# BodyTempUnit.net
KiCad netlist of a schematic drawn in EAGLE
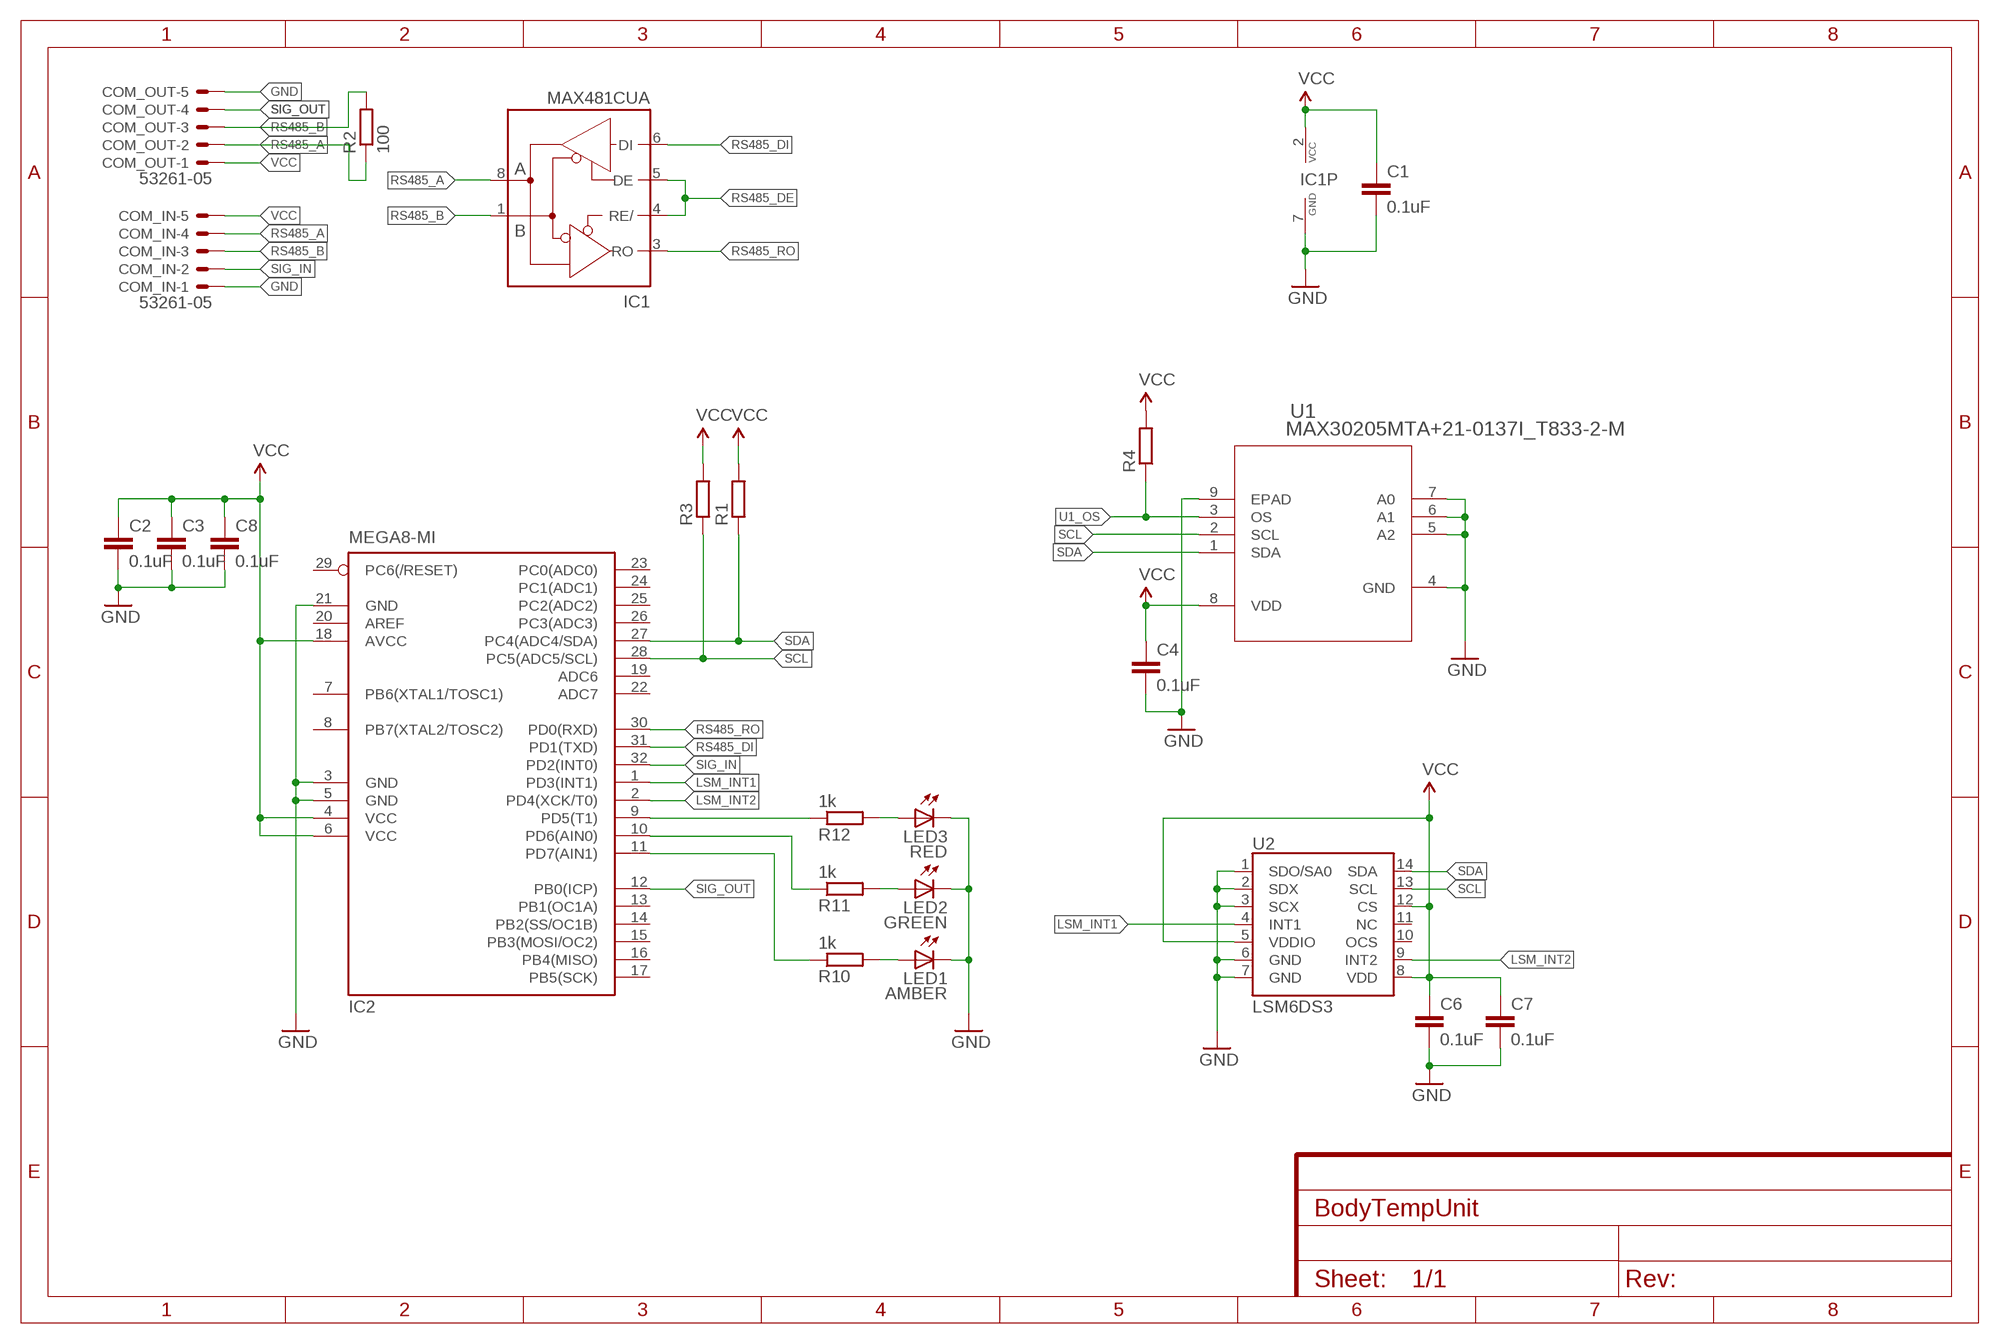
[diagram p0: schematic, sheet 1]

(export (version "E")
  (design (tool "Eeschema 10.0.6"))
  (components
    (comp (ref "C1")
      (value "0.1uF")
      (footprint "eagle-import:C0603K")
      (libsource (lib "eagle-import") (part "C-EUC0603K"))
    )
    (comp (ref "C2")
      (value "0.1uF")
      (footprint "eagle-import:C0603K")
      (libsource (lib "eagle-import") (part "C-EUC0603K"))
    )
    (comp (ref "C3")
      (value "0.1uF")
      (footprint "eagle-import:C0603K")
      (libsource (lib "eagle-import") (part "C-EUC0603K"))
    )
    (comp (ref "C4")
      (value "0.1uF")
      (footprint "eagle-import:C0603K")
      (libsource (lib "eagle-import") (part "C-EUC0603K"))
    )
    (comp (ref "C6")
      (value "0.1uF")
      (footprint "eagle-import:C0603K")
      (libsource (lib "eagle-import") (part "C-EUC0603K"))
    )
    (comp (ref "C7")
      (value "0.1uF")
      (footprint "eagle-import:C0603K")
      (libsource (lib "eagle-import") (part "C-EUC0603K"))
    )
    (comp (ref "C8")
      (value "0.1uF")
      (footprint "eagle-import:C0603K")
      (libsource (lib "eagle-import") (part "C-EUC0603K"))
    )
    (comp (ref "COM_IN")
      (value "53261-05")
      (footprint "eagle-import:53261-05")
      (fields (field (name "MF") "MOLEX"))
      (libsource (lib "eagle-import") (part "53?-05261"))
    )
    (comp (ref "COM_OUT")
      (value "53261-05")
      (footprint "eagle-import:53261-05")
      (fields (field (name "MF") "MOLEX"))
      (libsource (lib "eagle-import") (part "53?-05261"))
    )
    (comp (ref "IC1")
      (value "MAX481CUA")
      (footprint "eagle-import:UMAX8")
      (fields (field (name "MPN") "MAX481CUA+"))
      (libsource (lib "eagle-import") (part "MAX481CUA"))
    )
    (comp (ref "IC2")
      (value "MEGA8-MI")
      (footprint "eagle-import:MLF32")
      (fields (field (name "MPN") "ATMEGA88PA-MU"))
      (libsource (lib "eagle-import") (part "MEGA8-MI"))
    )
    (comp (ref "LED1")
      (value "AMBER")
      (footprint "eagle-import:CHIPLED_0603")
      (libsource (lib "eagle-import") (part "LEDCHIPLED_0603"))
    )
    (comp (ref "LED2")
      (value "GREEN")
      (footprint "eagle-import:CHIPLED_0603")
      (libsource (lib "eagle-import") (part "LEDCHIPLED_0603"))
    )
    (comp (ref "LED3")
      (value "RED")
      (footprint "eagle-import:CHIPLED_0603")
      (libsource (lib "eagle-import") (part "LEDCHIPLED_0603"))
    )
    (comp (ref "R1")
      (value "R-EU_R0603")
      (footprint "eagle-import:R0603")
      (libsource (lib "eagle-import") (part "rcl_334_R-EU_R0603"))
    )
    (comp (ref "R2")
      (value "100")
      (footprint "eagle-import:R0603")
      (libsource (lib "eagle-import") (part "rcl_334_R-EU_R0603"))
    )
    (comp (ref "R3")
      (value "R-EU_R0603")
      (footprint "eagle-import:R0603")
      (libsource (lib "eagle-import") (part "rcl_334_R-EU_R0603"))
    )
    (comp (ref "R4")
      (value "R-EU_R0603")
      (footprint "eagle-import:R0603")
      (libsource (lib "eagle-import") (part "rcl_334_R-EU_R0603"))
    )
    (comp (ref "R10")
      (value "1k")
      (footprint "eagle-import:R0603")
      (libsource (lib "eagle-import") (part "R-EU_R0603"))
    )
    (comp (ref "R11")
      (value "1k")
      (footprint "eagle-import:R0603")
      (libsource (lib "eagle-import") (part "R-EU_R0603"))
    )
    (comp (ref "R12")
      (value "1k")
      (footprint "eagle-import:R0603")
      (libsource (lib "eagle-import") (part "R-EU_R0603"))
    )
    (comp (ref "U1")
      (value "MAX30205MTA+21-0137I_T833-2-M")
      (footprint "eagle-import:21-0137I_T833-2-M")
      (fields (field (name "MANUFACTURER_PART_NUMBER") "MAX30205MTA+"))
      (libsource (lib "eagle-import") (part "MAX30205MTA+21-0137I_T833-2-M"))
    )
    (comp (ref "U2")
      (value "LSM6DS3")
      (footprint "eagle-import:LGA14L")
      (libsource (lib "eagle-import") (part "LSM6DS3"))
    )
  )
  (nets
    (net (code "1") (name "GND") (class "Default")
      (node (ref "C1") (pin "2") (pinfunction "2_2") (pintype "passive"))
      (node (ref "C2") (pin "2") (pinfunction "2_2") (pintype "passive"))
      (node (ref "C3") (pin "2") (pinfunction "2_2") (pintype "passive"))
      (node (ref "C4") (pin "2") (pinfunction "2_2") (pintype "passive"))
      (node (ref "C6") (pin "2") (pinfunction "2_2") (pintype "passive"))
      (node (ref "C7") (pin "2") (pinfunction "2_2") (pintype "passive"))
      (node (ref "C8") (pin "2") (pinfunction "2_2") (pintype "passive"))
      (node (ref "COM_IN") (pin "1") (pinfunction "S_1") (pintype "passive"))
      (node (ref "COM_OUT") (pin "5") (pinfunction "S_5") (pintype "passive"))
      (node (ref "IC1") (pin "7") (pinfunction "GND_7") (pintype "power_in"))
      (node (ref "IC2") (pin "21") (pinfunction "GND_21") (pintype "power_in"))
      (node (ref "IC2") (pin "3") (pinfunction "GND_3") (pintype "power_in"))
      (node (ref "IC2") (pin "5") (pinfunction "GND_5") (pintype "power_in"))
      (node (ref "LED1") (pin "C") (pinfunction "C_C") (pintype "passive"))
      (node (ref "LED2") (pin "C") (pinfunction "C_C") (pintype "passive"))
      (node (ref "LED3") (pin "C") (pinfunction "C_C") (pintype "passive"))
      (node (ref "U1") (pin "4") (pinfunction "GND_4") (pintype "passive"))
      (node (ref "U1") (pin "5") (pinfunction "A2_5") (pintype "bidirectional"))
      (node (ref "U1") (pin "6") (pinfunction "A1_6") (pintype "bidirectional"))
      (node (ref "U1") (pin "7") (pinfunction "A0_7") (pintype "bidirectional"))
      (node (ref "U1") (pin "9") (pinfunction "EPAD_9") (pintype "passive"))
      (node (ref "U2") (pin "1") (pinfunction "SDO/SA0_1") (pintype "bidirectional"))
      (node (ref "U2") (pin "2") (pinfunction "SDX_2") (pintype "bidirectional"))
      (node (ref "U2") (pin "3") (pinfunction "SCX_3") (pintype "bidirectional"))
      (node (ref "U2") (pin "6") (pinfunction "GND_6") (pintype "bidirectional"))
      (node (ref "U2") (pin "7") (pinfunction "GND_7") (pintype "bidirectional"))
    )
    (net (code "2") (name "LSM_INT1") (class "Default")
      (node (ref "IC2") (pin "1") (pinfunction "PD3(INT1)_1") (pintype "bidirectional"))
      (node (ref "U2") (pin "4") (pinfunction "INT1_4") (pintype "bidirectional"))
    )
    (net (code "3") (name "LSM_INT2") (class "Default")
      (node (ref "IC2") (pin "2") (pinfunction "PD4(XCK/T0)_2") (pintype "bidirectional"))
      (node (ref "U2") (pin "9") (pinfunction "INT2_9") (pintype "bidirectional"))
    )
    (net (code "4") (name "Net-(IC2-PD5(T1))") (class "Default")
      (node (ref "IC2") (pin "9") (pinfunction "PD5(T1)_9") (pintype "bidirectional"))
      (node (ref "R12") (pin "1") (pinfunction "1_1") (pintype "passive"))
    )
    (net (code "5") (name "Net-(IC2-PD6(AIN0))") (class "Default")
      (node (ref "IC2") (pin "10") (pinfunction "PD6(AIN0)_10") (pintype "bidirectional"))
      (node (ref "R11") (pin "1") (pinfunction "1_1") (pintype "passive"))
    )
    (net (code "6") (name "Net-(IC2-PD7(AIN1))") (class "Default")
      (node (ref "IC2") (pin "11") (pinfunction "PD7(AIN1)_11") (pintype "bidirectional"))
      (node (ref "R10") (pin "1") (pinfunction "1_1") (pintype "passive"))
    )
    (net (code "7") (name "Net-(LED1-PadA)") (class "Default")
      (node (ref "LED1") (pin "A") (pinfunction "A_A") (pintype "passive"))
      (node (ref "R10") (pin "2") (pinfunction "2_2") (pintype "passive"))
    )
    (net (code "8") (name "Net-(LED2-PadA)") (class "Default")
      (node (ref "LED2") (pin "A") (pinfunction "A_A") (pintype "passive"))
      (node (ref "R11") (pin "2") (pinfunction "2_2") (pintype "passive"))
    )
    (net (code "9") (name "Net-(LED3-PadA)") (class "Default")
      (node (ref "LED3") (pin "A") (pinfunction "A_A") (pintype "passive"))
      (node (ref "R12") (pin "2") (pinfunction "2_2") (pintype "passive"))
    )
    (net (code "10") (name "RS485_A") (class "Default")
      (node (ref "COM_IN") (pin "4") (pinfunction "S_4") (pintype "passive"))
      (node (ref "COM_OUT") (pin "2") (pinfunction "S_2") (pintype "passive"))
      (node (ref "IC1") (pin "8") (pinfunction "A_8") (pintype "passive"))
      (node (ref "R2") (pin "1") (pinfunction "1_1") (pintype "passive"))
    )
    (net (code "11") (name "RS485_B") (class "Default")
      (node (ref "COM_IN") (pin "3") (pinfunction "S_3") (pintype "passive"))
      (node (ref "COM_OUT") (pin "3") (pinfunction "S_3") (pintype "passive"))
      (node (ref "IC1") (pin "1") (pinfunction "B_1") (pintype "passive"))
      (node (ref "R2") (pin "2") (pinfunction "2_2") (pintype "passive"))
    )
    (net (code "12") (name "RS485_DE") (class "Default")
      (node (ref "IC1") (pin "4") (pinfunction "RE/_4") (pintype "input"))
      (node (ref "IC1") (pin "5") (pinfunction "DE_5") (pintype "input"))
    )
    (net (code "13") (name "RS485_DI") (class "Default")
      (node (ref "IC1") (pin "6") (pinfunction "DI_6") (pintype "input"))
      (node (ref "IC2") (pin "31") (pinfunction "PD1(TXD)_31") (pintype "bidirectional"))
    )
    (net (code "14") (name "RS485_RO") (class "Default")
      (node (ref "IC1") (pin "3") (pinfunction "RO_3") (pintype "output"))
      (node (ref "IC2") (pin "30") (pinfunction "PD0(RXD)_30") (pintype "bidirectional"))
    )
    (net (code "15") (name "SCL") (class "Default")
      (node (ref "IC2") (pin "28") (pinfunction "PC5(ADC5/SCL)_28") (pintype "bidirectional"))
      (node (ref "R3") (pin "1") (pinfunction "1_1") (pintype "passive"))
      (node (ref "U1") (pin "2") (pinfunction "SCL_2") (pintype "passive"))
      (node (ref "U2") (pin "13") (pinfunction "SCL_13") (pintype "bidirectional"))
    )
    (net (code "16") (name "SDA") (class "Default")
      (node (ref "IC2") (pin "27") (pinfunction "PC4(ADC4/SDA)_27") (pintype "bidirectional"))
      (node (ref "R1") (pin "1") (pinfunction "1_1") (pintype "passive"))
      (node (ref "U1") (pin "1") (pinfunction "SDA_1") (pintype "passive"))
      (node (ref "U2") (pin "14") (pinfunction "SDA_14") (pintype "bidirectional"))
    )
    (net (code "17") (name "SIG_IN") (class "Default")
      (node (ref "COM_IN") (pin "2") (pinfunction "S_2") (pintype "passive"))
      (node (ref "IC2") (pin "32") (pinfunction "PD2(INT0)_32") (pintype "bidirectional"))
    )
    (net (code "18") (name "SIG_OUT") (class "Default")
      (node (ref "COM_OUT") (pin "4") (pinfunction "S_4") (pintype "passive"))
      (node (ref "IC2") (pin "12") (pinfunction "PB0(ICP)_12") (pintype "bidirectional"))
    )
    (net (code "19") (name "U1_OS") (class "Default")
      (node (ref "R4") (pin "1") (pinfunction "1_1") (pintype "passive"))
      (node (ref "U1") (pin "3") (pinfunction "OS_3") (pintype "passive"))
    )
    (net (code "20") (name "VCC") (class "Default")
      (node (ref "C1") (pin "1") (pinfunction "1_1") (pintype "passive"))
      (node (ref "C2") (pin "1") (pinfunction "1_1") (pintype "passive"))
      (node (ref "C3") (pin "1") (pinfunction "1_1") (pintype "passive"))
      (node (ref "C4") (pin "1") (pinfunction "1_1") (pintype "passive"))
      (node (ref "C6") (pin "1") (pinfunction "1_1") (pintype "passive"))
      (node (ref "C7") (pin "1") (pinfunction "1_1") (pintype "passive"))
      (node (ref "C8") (pin "1") (pinfunction "1_1") (pintype "passive"))
      (node (ref "COM_IN") (pin "5") (pinfunction "S_5") (pintype "passive"))
      (node (ref "COM_OUT") (pin "1") (pinfunction "S_1") (pintype "passive"))
      (node (ref "IC1") (pin "2") (pinfunction "VCC_2") (pintype "power_in"))
      (node (ref "IC2") (pin "18") (pinfunction "AVCC_18") (pintype "power_in"))
      (node (ref "IC2") (pin "4") (pinfunction "VCC_4") (pintype "power_in"))
      (node (ref "IC2") (pin "6") (pinfunction "VCC_6") (pintype "power_in"))
      (node (ref "R1") (pin "2") (pinfunction "2_2") (pintype "passive"))
      (node (ref "R3") (pin "2") (pinfunction "2_2") (pintype "passive"))
      (node (ref "R4") (pin "2") (pinfunction "2_2") (pintype "passive"))
      (node (ref "U1") (pin "8") (pinfunction "VDD_8") (pintype "power_in"))
      (node (ref "U2") (pin "12") (pinfunction "CS_12") (pintype "bidirectional"))
      (node (ref "U2") (pin "5") (pinfunction "VDDIO_5") (pintype "bidirectional"))
      (node (ref "U2") (pin "8") (pinfunction "VDD_8") (pintype "bidirectional"))
    )
    (net (code "21") (name "unconnected-(IC2-ADC6-Pad19)") (class "Default")
      (node (ref "IC2") (pin "19") (pinfunction "ADC6_19") (pintype "bidirectional"))
    )
    (net (code "22") (name "unconnected-(IC2-ADC7-Pad22)") (class "Default")
      (node (ref "IC2") (pin "22") (pinfunction "ADC7_22") (pintype "bidirectional"))
    )
    (net (code "23") (name "unconnected-(IC2-AREF-Pad20)") (class "Default")
      (node (ref "IC2") (pin "20") (pinfunction "AREF_20") (pintype "passive"))
    )
    (net (code "24") (name "unconnected-(IC2-PB1(OC1A)-Pad13)") (class "Default")
      (node (ref "IC2") (pin "13") (pinfunction "PB1(OC1A)_13") (pintype "bidirectional"))
    )
    (net (code "25") (name "unconnected-(IC2-PB2(SS{slash}OC1B)-Pad14)") (class "Default")
      (node (ref "IC2") (pin "14") (pinfunction "PB2(SS/OC1B)_14") (pintype "bidirectional"))
    )
    (net (code "26") (name "unconnected-(IC2-PB3(MOSI{slash}OC2)-Pad15)") (class "Default")
      (node (ref "IC2") (pin "15") (pinfunction "PB3(MOSI/OC2)_15") (pintype "bidirectional"))
    )
    (net (code "27") (name "unconnected-(IC2-PB4(MISO)-Pad16)") (class "Default")
      (node (ref "IC2") (pin "16") (pinfunction "PB4(MISO)_16") (pintype "bidirectional"))
    )
    (net (code "28") (name "unconnected-(IC2-PB5(SCK)-Pad17)") (class "Default")
      (node (ref "IC2") (pin "17") (pinfunction "PB5(SCK)_17") (pintype "bidirectional"))
    )
    (net (code "29") (name "unconnected-(IC2-PB6(XTAL1{slash}TOSC1)-Pad7)") (class "Default")
      (node (ref "IC2") (pin "7") (pinfunction "PB6(XTAL1/TOSC1)_7") (pintype "bidirectional"))
    )
    (net (code "30") (name "unconnected-(IC2-PB7(XTAL2{slash}TOSC2)-Pad8)") (class "Default")
      (node (ref "IC2") (pin "8") (pinfunction "PB7(XTAL2/TOSC2)_8") (pintype "bidirectional"))
    )
    (net (code "31") (name "unconnected-(IC2-PC0(ADC0)-Pad23)") (class "Default")
      (node (ref "IC2") (pin "23") (pinfunction "PC0(ADC0)_23") (pintype "bidirectional"))
    )
    (net (code "32") (name "unconnected-(IC2-PC1(ADC1)-Pad24)") (class "Default")
      (node (ref "IC2") (pin "24") (pinfunction "PC1(ADC1)_24") (pintype "bidirectional"))
    )
    (net (code "33") (name "unconnected-(IC2-PC2(ADC2)-Pad25)") (class "Default")
      (node (ref "IC2") (pin "25") (pinfunction "PC2(ADC2)_25") (pintype "bidirectional"))
    )
    (net (code "34") (name "unconnected-(IC2-PC3(ADC3)-Pad26)") (class "Default")
      (node (ref "IC2") (pin "26") (pinfunction "PC3(ADC3)_26") (pintype "bidirectional"))
    )
    (net (code "35") (name "unconnected-(IC2-PC6({slash}RESET)-Pad29)") (class "Default")
      (node (ref "IC2") (pin "29") (pinfunction "PC6(/RESET)_29") (pintype "bidirectional"))
    )
    (net (code "36") (name "unconnected-(U2-NC-Pad11)") (class "Default")
      (node (ref "U2") (pin "11") (pinfunction "NC_11") (pintype "bidirectional"))
    )
    (net (code "37") (name "unconnected-(U2-OCS-Pad10)") (class "Default")
      (node (ref "U2") (pin "10") (pinfunction "OCS_10") (pintype "bidirectional"))
    )
  )
)
